# RTC.net
KiCad netlist of a schematic drawn in Altium Designer
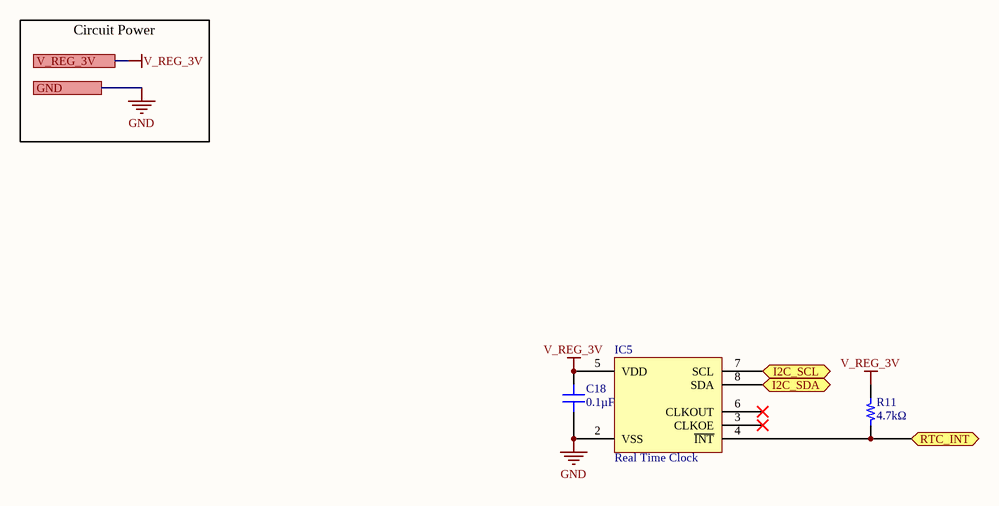
[diagram p0: RTC.SchDoc]

(export (version "E")
  (design (tool "Eeschema 10.0.6"))
  (components
    (comp (ref "C18")
      (value "0.1µF")
      (footprint "CAP 0402_1005")
      (description "CAP CER 0.1UF 16V X7R 0402")
      (fields (field (name "MANUFACTURER") "KEMET") (field (name "VOLTAGE") "16V"))
      (libsource (lib "MVVVMAltiumDatabase") (part "Capacitor"))
    )
    (comp (ref "IC5")
      (value "Real Time Clock")
      (footprint "MICRO CRYSTAL 8-SON")
      (description "IC RTC CLK/CALENDAR I2C 8-SMT")
      (fields (field (name "MANUFACTURER") "Micro Crystal AG"))
      (libsource (lib "MVVVMAltiumDatabase") (part "Micro Crystal AG RV-8263-C7-32.768KHZ-20PPM-TA-QC"))
    )
    (comp (ref "R11")
      (value "4.7kΩ")
      (footprint "RES 0402_1005 RF")
      (description "RES SMD 4.7K OHM 1% 1/8W 0402")
      (fields (field (name "MANUFACTURER") "YAGEO") (field (name "TOLERANCE") "±1%"))
      (libsource (lib "MVVVMAltiumDatabase") (part "Resistor"))
    )
  )
  (nets
    (net (code "1") (name "/I2C_SCL") (class "Default")
      (node (ref "IC5") (pin "7") (pinfunction "SCL_7") (pintype "passive"))
    )
    (net (code "2") (name "/I2C_SDA") (class "Default")
      (node (ref "IC5") (pin "8") (pinfunction "SDA_8") (pintype "passive"))
    )
    (net (code "3") (name "/RTC_INT") (class "Default")
      (node (ref "IC5") (pin "4") (pinfunction "~{INT}_4") (pintype "passive"))
      (node (ref "R11") (pin "1") (pinfunction "1_1") (pintype "passive"))
    )
    (net (code "4") (name "GND") (class "Default")
      (node (ref "C18") (pin "1") (pinfunction "1_1") (pintype "passive"))
      (node (ref "IC5") (pin "2") (pinfunction "VSS_2") (pintype "passive"))
    )
    (net (code "5") (name "V_REG_3V") (class "Default")
      (node (ref "C18") (pin "2") (pinfunction "2_2") (pintype "passive"))
      (node (ref "IC5") (pin "5") (pinfunction "VDD_5") (pintype "passive"))
      (node (ref "R11") (pin "2") (pinfunction "2_2") (pintype "passive"))
    )
    (net (code "6") (name "unconnected-(IC5-CLKOE-Pad3)") (class "Default")
      (node (ref "IC5") (pin "3") (pinfunction "CLKOE_3") (pintype "passive+no_connect"))
    )
    (net (code "7") (name "unconnected-(IC5-CLKOUT-Pad6)") (class "Default")
      (node (ref "IC5") (pin "6") (pinfunction "CLKOUT_6") (pintype "passive+no_connect"))
    )
  )
)
